# block_statut_led.net
KiCad netlist of a schematic drawn in EAGLE
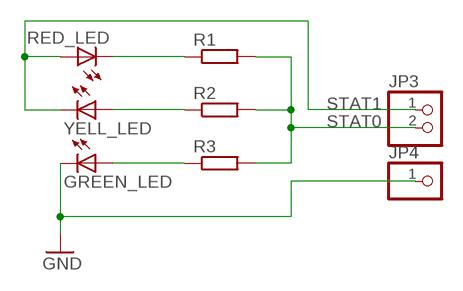
[diagram p0: schematic, sheet 1]

(export (version "E")
  (design (tool "Eeschema 10.0.6"))
  (components
    (comp (ref "GREEN_LED")
      (value "LED3MM")
      (footprint "eagle-import:LED3MM")
      (libsource (lib "eagle-import") (part "LED3MM"))
    )
    (comp (ref "JP3")
      (value "PINHD-1X2")
      (footprint "eagle-import:1X02")
      (libsource (lib "eagle-import") (part "PINHD-1X2"))
    )
    (comp (ref "JP4")
      (value "PINHD-1X1")
      (footprint "eagle-import:1X01")
      (libsource (lib "eagle-import") (part "PINHD-1X1"))
    )
    (comp (ref "R1")
      (value "R-EU_0207/5V")
      (footprint "eagle-import:0207_5V")
      (libsource (lib "eagle-import") (part "R-EU_0207/5V"))
    )
    (comp (ref "R2")
      (value "R-EU_0207/5V")
      (footprint "eagle-import:0207_5V")
      (libsource (lib "eagle-import") (part "R-EU_0207/5V"))
    )
    (comp (ref "R3")
      (value "R-EU_0207/5V")
      (footprint "eagle-import:0207_5V")
      (libsource (lib "eagle-import") (part "R-EU_0207/5V"))
    )
    (comp (ref "RED_LED")
      (value "LED3MM")
      (footprint "eagle-import:LED3MM")
      (libsource (lib "eagle-import") (part "LED3MM"))
    )
    (comp (ref "YELL_LED")
      (value "LED3MM")
      (footprint "eagle-import:LED3MM")
      (libsource (lib "eagle-import") (part "LED3MM"))
    )
  )
  (nets
    (net (code "1") (name "/STAT0") (class "Default")
      (node (ref "JP3") (pin "2") (pinfunction "2_2") (pintype "passive"))
      (node (ref "R1") (pin "2") (pinfunction "2_2") (pintype "passive"))
      (node (ref "R2") (pin "2") (pinfunction "2_2") (pintype "passive"))
      (node (ref "R3") (pin "2") (pinfunction "2_2") (pintype "passive"))
    )
    (net (code "2") (name "/STAT1") (class "Default")
      (node (ref "JP3") (pin "1") (pinfunction "1_1") (pintype "passive"))
      (node (ref "RED_LED") (pin "A") (pinfunction "A_A") (pintype "passive"))
      (node (ref "YELL_LED") (pin "K") (pinfunction "C_K") (pintype "passive"))
    )
    (net (code "3") (name "GND") (class "Default")
      (node (ref "GREEN_LED") (pin "K") (pinfunction "C_K") (pintype "passive"))
      (node (ref "JP4") (pin "1") (pinfunction "1_1") (pintype "passive"))
    )
    (net (code "4") (name "Net-(GREEN_LED-PadA)") (class "Default")
      (node (ref "GREEN_LED") (pin "A") (pinfunction "A_A") (pintype "passive"))
      (node (ref "R3") (pin "1") (pinfunction "1_1") (pintype "passive"))
    )
    (net (code "5") (name "Net-(R2-Pad1)") (class "Default")
      (node (ref "R2") (pin "1") (pinfunction "1_1") (pintype "passive"))
      (node (ref "YELL_LED") (pin "A") (pinfunction "A_A") (pintype "passive"))
    )
    (net (code "6") (name "Net-(RED_LED-C)") (class "Default")
      (node (ref "R1") (pin "1") (pinfunction "1_1") (pintype "passive"))
      (node (ref "RED_LED") (pin "K") (pinfunction "C_K") (pintype "passive"))
    )
  )
)
